# 51_V4.net
KiCad netlist of a schematic drawn in EasyEDA Pro
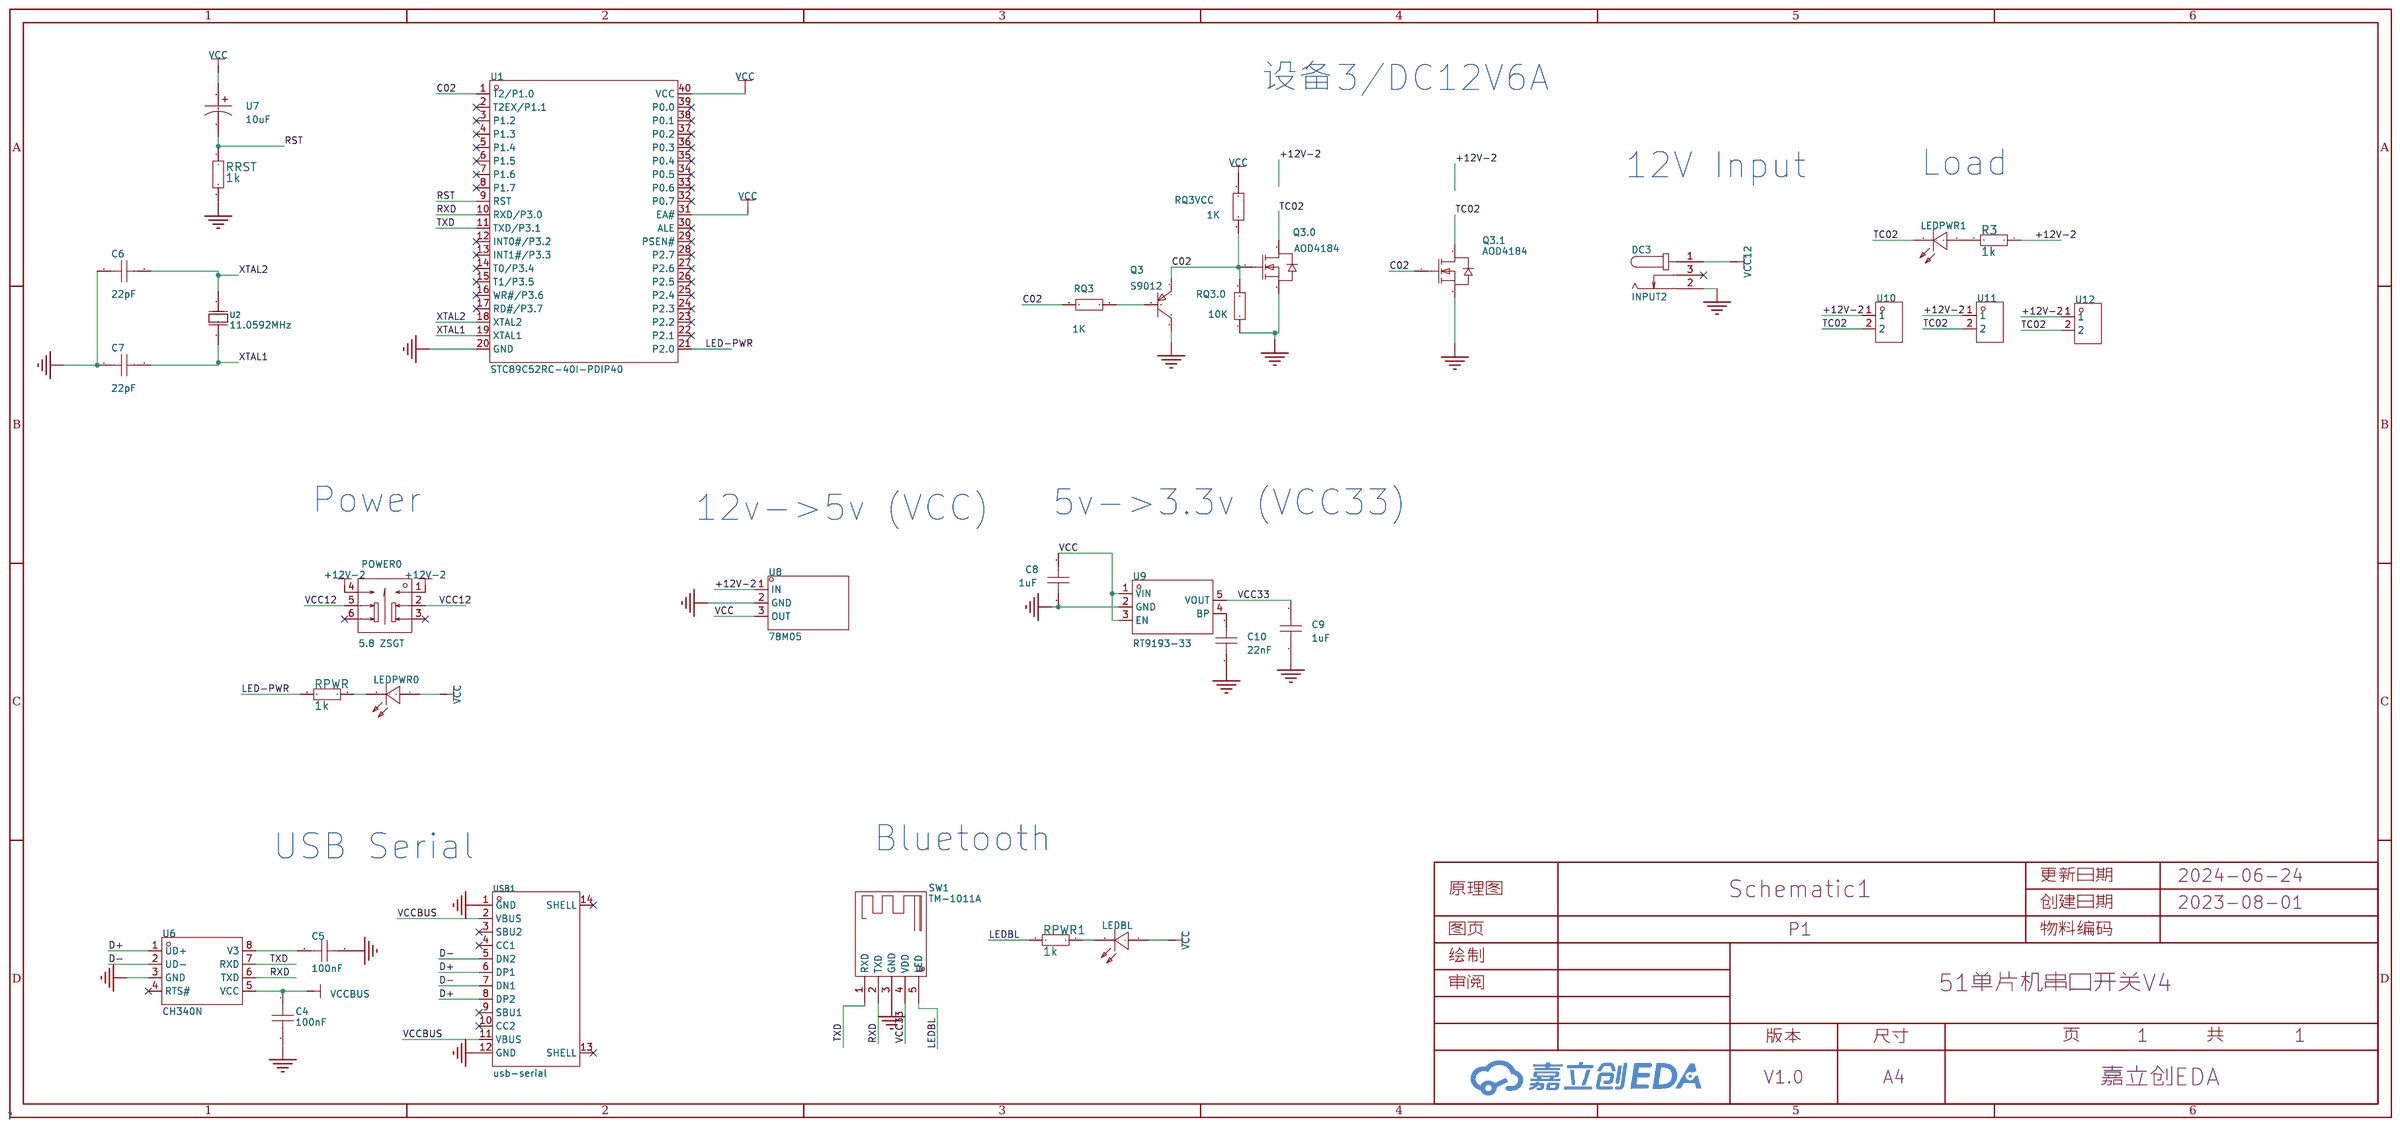
[diagram p0: schematic sheet]

(export (version "E")
  (design (tool "Eeschema 10.0.6"))
  (components
    (comp (ref "C4")
      (value "100nF")
      (footprint "easyedapro:C0603")
      (libsource (lib "easyedapro") (part "CapAcitance"))
    )
    (comp (ref "C5")
      (value "100nF")
      (footprint "easyedapro:C0603")
      (libsource (lib "easyedapro") (part "CapAcitance"))
    )
    (comp (ref "C6")
      (value "22pF")
      (footprint "easyedapro:CAP-TH_L5.8-W2.4-P2.54-D0.6")
      (description "容值:22pF;精度:±10%;额定电压:50V;温度系数:NP0;")
      (fields
        (field (name "Manufacturer Part") "CC1H220KA1EDCH4B1100")
        (field (name "Manufacturer") "Dersonic(德尔创)")
      )
      (libsource (lib "easyedapro") (part "CC1H220KA1EDCH4B1100"))
    )
    (comp (ref "C7")
      (value "22pF")
      (footprint "easyedapro:CAP-TH_L5.8-W2.4-P2.54-D0.6")
      (description "容值:22pF;精度:±10%;额定电压:50V;温度系数:NP0;")
      (fields
        (field (name "Manufacturer Part") "CC1H220KA1EDCH4B1100")
        (field (name "Manufacturer") "Dersonic(德尔创)")
      )
      (libsource (lib "easyedapro") (part "CC1H220KA1EDCH4B1100"))
    )
    (comp (ref "C8")
      (value "1uF")
      (footprint "easyedapro:C0603")
      (libsource (lib "easyedapro") (part "CapAcitance"))
    )
    (comp (ref "C9")
      (value "1uF")
      (footprint "easyedapro:C0603")
      (libsource (lib "easyedapro") (part "CapAcitance"))
    )
    (comp (ref "C10")
      (value "22nF")
      (footprint "easyedapro:C0603")
      (libsource (lib "easyedapro") (part "CapAcitance"))
    )
    (comp (ref "DC3")
      (value "INPUT2")
      (footprint "easyedapro:DC-IN-TH_DC-005-20A")
      (description "触点内径:2mm;触点外径:6.4mm;额定电流:500mA;额定电压:30V;")
      (fields (field (name "Manufacturer Part") "DC-005-20A") (field (name "Manufacturer") "韩国韩荣"))
      (libsource (lib "easyedapro") (part "DC-005-20A_C136744"))
    )
    (comp (ref "LEDBL")
      (value "Φ3mm直插蓝色发光二极管")
      (footprint "easyedapro:LED-TH_BD4.1-P2.50-D0.5-FD_BULE")
      (libsource (lib "easyedapro") (part "Φ3MM直插蓝色发光二极管"))
    )
    (comp (ref "LEDPWR0")
      (value "Φ3mm直插蓝色发光二极管")
      (footprint "easyedapro:LED-TH_BD4.1-P2.50-D0.5-FD_BULE")
      (libsource (lib "easyedapro") (part "Φ3MM直插蓝色发光二极管"))
    )
    (comp (ref "LEDPWR1")
      (value "Φ3mm直插蓝色发光二极管")
      (footprint "easyedapro:LED-TH_BD4.1-P2.50-D0.5-FD_BULE")
      (libsource (lib "easyedapro") (part "Φ3MM直插蓝色发光二极管"))
    )
    (comp (ref "POWER0")
      (value "5.8 ZSGT")
      (footprint "easyedapro:SW-TH_5.8ZSGT")
      (fields (field (name "Manufacturer") "SHOU HAN(首韩)"))
      (libsource (lib "easyedapro") (part "5.8 ZSGT"))
    )
    (comp (ref "Q3")
      (value "S9012")
      (footprint "easyedapro:TO-92-3_L4.6-W3.6-P1.27-L-1")
      (fields (field (name "Manufacturer") "JSMSEMI(杰盛微)"))
      (libsource (lib "easyedapro") (part "S9012_C2931496"))
    )
    (comp (ref "Q3.0")
      (value "AOD4184")
      (footprint "easyedapro:TO-252-2_L6.6-W6.1-P4.58-LS9.9-BR")
      (fields (field (name "Manufacturer") "VBsemi(微碧)"))
      (libsource (lib "easyedapro") (part "AOD4184"))
    )
    (comp (ref "Q3.1")
      (value "AOD4184")
      (footprint "easyedapro:TO-252-2_L6.6-W6.1-P4.58-LS9.9-BR")
      (fields (field (name "Manufacturer") "VBsemi(微碧)"))
      (libsource (lib "easyedapro") (part "AOD4184"))
    )
    (comp (ref "R3")
      (value "1k")
      (footprint "easyedapro:0603")
      (description "Resistor")
      (libsource (lib "easyedapro") (part "RES"))
    )
    (comp (ref "RPWR")
      (value "1k")
      (footprint "easyedapro:0603")
      (description "Resistor")
      (libsource (lib "easyedapro") (part "RES"))
    )
    (comp (ref "RPWR1")
      (value "1k")
      (footprint "easyedapro:0603")
      (description "Resistor")
      (libsource (lib "easyedapro") (part "RES"))
    )
    (comp (ref "RQ3") (value "1K") (footprint "easyedapro:R0603") (libsource (lib "easyedapro") (part "电阻")))
    (comp (ref "RQ3.0")
      (value "10K")
      (footprint "easyedapro:R0603")
      (libsource (lib "easyedapro") (part "电阻"))
    )
    (comp (ref "RQ3VCC")
      (value "1K")
      (footprint "easyedapro:R0603")
      (libsource (lib "easyedapro") (part "电阻"))
    )
    (comp (ref "RRST")
      (value "1k")
      (footprint "easyedapro:0603")
      (description "Resistor")
      (libsource (lib "easyedapro") (part "RES"))
    )
    (comp (ref "SW1")
      (value "TM-1011A")
      (footprint "easyedapro:SW-SMD_TM-1011A")
      (description "6328A低成本蓝牙模块")
      (fields (field (name "Manufacturer") "XKB Connectivity(中国星坤)") (field (name "NAME") "LED"))
      (libsource (lib "easyedapro") (part "邮票5孔蓝牙模块"))
    )
    (comp (ref "U1")
      (value "STC89C52RC-40I-PDIP40")
      (footprint "easyedapro:DIP-40_L52.0-W13.7-P2.54-LS15.2-BL")
      (fields (field (name "Manufacturer") "STC(宏晶)"))
      (libsource (lib "easyedapro") (part "STC89C52RC-40I"))
    )
    (comp (ref "U2")
      (value "11.0592MHz")
      (footprint "easyedapro:CRYSTAL-TH_L10.8-W4.5-P4.88")
      (description "频率:10MHz;频率公差:±30ppm;负载电容:18pF;")
      (fields (field (name "Manufacturer Part") "ATS100B-E") (field (name "Manufacturer") "CTS(西迪斯)"))
      (libsource (lib "easyedapro") (part "ATS100B-E"))
    )
    (comp (ref "U6")
      (value "CH340N")
      (footprint "easyedapro:SOP-8_L4.9-W3.9-P1.27-LS6.0-BL")
      (fields (field (name "Manufacturer") "WCH(南京沁恒)"))
      (libsource (lib "easyedapro") (part "CH340N_C2977777"))
    )
    (comp (ref "U7")
      (value "10uF")
      (footprint "easyedapro:CAP-TH_BD6.3-P2.50-D0.5-FD")
      (description "容值:10uF;精度:±20%;额定电压:50V;纹波电流:-;等效串联电阻:-;")
      (fields
        (field (name "Manufacturer Part") "ESK106M1HD11RRSNP-R")
        (field (name "Manufacturer") "MAN YUE(万裕科技)")
      )
      (libsource (lib "easyedapro") (part "ESK106M1HD11RRSNP-R"))
    )
    (comp (ref "U8")
      (value "78M05")
      (footprint "easyedapro:TO-252-2_L6.6-W6.1-P4.57-LS9.9-BR-CW")
      (description "输出类型:固定;最大输入电压:35V;输出电压:5V;最大输出电流:1A;电源纹波抑制比(PSRR):80dB@(120Hz);输出极性:正极;")
      (fields (field (name "Manufacturer") "UMW(友台半导体)"))
      (libsource (lib "easyedapro") (part "UMW78M05"))
    )
    (comp (ref "U9")
      (value "RT9193-33")
      (footprint "easyedapro:SOT-23-5_L2.9-W1.6-P0.95-LS2.8-BL")
      (libsource (lib "easyedapro") (part "RT9193-33"))
    )
    (comp (ref "U10")
      (value "HX 2.54mm-2P ZZ-MS")
      (footprint "easyedapro:CONN-TH_2P-P2.50_HX-2.54MM-2P-ZZ-MS")
      (description "插针结构:1x2P;间距:2.5mm;安装方式:直插;参考系列:XH;总PIN数:2P;排数:1;每排PIN数:2;额定电流:3A;工作温度范围:-25°C~+85°C;")
      (fields (field (name "Manufacturer") "hanxia(韩下)"))
      (libsource (lib "easyedapro") (part "HX 2.54MM-2P ZZ-MS"))
    )
    (comp (ref "U11")
      (value "HX 2.54mm-2P ZZ-MS")
      (footprint "easyedapro:CONN-TH_2P-P2.50_HX-2.54MM-2P-ZZ-MS")
      (description "插针结构:1x2P;间距:2.5mm;安装方式:直插;参考系列:XH;总PIN数:2P;排数:1;每排PIN数:2;额定电流:3A;工作温度范围:-25°C~+85°C;")
      (fields (field (name "Manufacturer") "hanxia(韩下)"))
      (libsource (lib "easyedapro") (part "HX 2.54MM-2P ZZ-MS"))
    )
    (comp (ref "U12")
      (value "HX 2.54mm-2P ZZ-MS")
      (footprint "easyedapro:CONN-TH_2P-P2.50_HX-2.54MM-2P-ZZ-MS")
      (description "插针结构:1x2P;间距:2.5mm;安装方式:直插;参考系列:XH;总PIN数:2P;排数:1;每排PIN数:2;额定电流:3A;工作温度范围:-25°C~+85°C;")
      (fields (field (name "Manufacturer") "hanxia(韩下)"))
      (libsource (lib "easyedapro") (part "HX 2.54MM-2P ZZ-MS"))
    )
    (comp (ref "USB1")
      (value "usb-serial")
      (footprint "easyedapro:USB-C-SMD_TYPE-C-6PIN-2MD-073")
      (description "连接器类型:Type-C;标准:-;公母:母座;触点数量:16;端口数量:1;安装方式:卧贴;额定电流 - 电源:5A;工作温度范围:-25°C~+85°C;")
      (fields
        (field (name "Manufacturer Part") "TYPE-C 16PIN 2MD(073)")
        (field (name "Manufacturer") "SHOU HAN(首韩)")
      )
      (libsource (lib "easyedapro") (part "TYPE-C 16PIN 2MD(073)"))
    )
  )
  (nets
    (net (code "1") (name "+12V-2") (class "Default")
      (node (ref "POWER0") (pin "1") (pinfunction "1_1") (pintype "input"))
      (node (ref "POWER0") (pin "4") (pinfunction "4_4") (pintype "input"))
      (node (ref "R3") (pin "1") (pinfunction "1_1") (pintype "input"))
      (node (ref "U10") (pin "1") (pinfunction "1_1") (pintype "unspecified"))
      (node (ref "U11") (pin "1") (pinfunction "1_1") (pintype "unspecified"))
      (node (ref "U12") (pin "1") (pinfunction "1_1") (pintype "unspecified"))
      (node (ref "U8") (pin "1") (pinfunction "IN_1") (pintype "unspecified"))
    )
    (net (code "2") (name "/C02") (class "Default")
      (node (ref "Q3") (pin "1") (pinfunction "E_1") (pintype "input"))
      (node (ref "Q3.0") (pin "1") (pinfunction "G_1") (pintype "input"))
      (node (ref "Q3.1") (pin "1") (pinfunction "G_1") (pintype "input"))
      (node (ref "RQ3") (pin "2") (pinfunction "2_2") (pintype "input"))
      (node (ref "RQ3.0") (pin "2") (pinfunction "2_2") (pintype "input"))
      (node (ref "RQ3VCC") (pin "1") (pinfunction "1_1") (pintype "input"))
      (node (ref "U1") (pin "1") (pinfunction "T2/P1.0_1") (pintype "input"))
    )
    (net (code "3") (name "/D+") (class "Default")
      (node (ref "U6") (pin "1") (pinfunction "UD+_1") (pintype "input"))
      (node (ref "USB1") (pin "6") (pinfunction "DP1_6") (pintype "input"))
      (node (ref "USB1") (pin "8") (pinfunction "DP2_8") (pintype "input"))
    )
    (net (code "4") (name "/D-") (class "Default")
      (node (ref "U6") (pin "2") (pinfunction "UD-_2") (pintype "input"))
      (node (ref "USB1") (pin "5") (pinfunction "DN2_5") (pintype "input"))
      (node (ref "USB1") (pin "7") (pinfunction "DN1_7") (pintype "input"))
    )
    (net (code "5") (name "/LED-PWR") (class "Default")
      (node (ref "RPWR") (pin "2") (pinfunction "2_2") (pintype "input"))
      (node (ref "U1") (pin "21") (pinfunction "P2.0_21") (pintype "input"))
    )
    (net (code "6") (name "/LEDBL") (class "Default")
      (node (ref "RPWR1") (pin "2") (pinfunction "2_2") (pintype "input"))
      (node (ref "SW1") (pin "5") (pinfunction "LED_5") (pintype "input"))
    )
    (net (code "7") (name "/RST") (class "Default")
      (node (ref "RRST") (pin "1") (pinfunction "1_1") (pintype "input"))
      (node (ref "U1") (pin "9") (pinfunction "RST_9") (pintype "input"))
      (node (ref "U7") (pin "2") (pinfunction "2_2") (pintype "input"))
    )
    (net (code "8") (name "/RXD") (class "Default")
      (node (ref "SW1") (pin "2") (pinfunction "TXD_2") (pintype "input"))
      (node (ref "U1") (pin "10") (pinfunction "RXD/P3.0_10") (pintype "input"))
      (node (ref "U6") (pin "6") (pinfunction "TXD_6") (pintype "input"))
    )
    (net (code "9") (name "/TC02") (class "Default")
      (node (ref "LEDPWR1") (pin "2") (pinfunction "-_2") (pintype "input"))
      (node (ref "Q3.0") (pin "2") (pinfunction "D_2") (pintype "input"))
      (node (ref "Q3.1") (pin "2") (pinfunction "D_2") (pintype "input"))
      (node (ref "U10") (pin "2") (pinfunction "2_2") (pintype "unspecified"))
      (node (ref "U11") (pin "2") (pinfunction "2_2") (pintype "unspecified"))
      (node (ref "U12") (pin "2") (pinfunction "2_2") (pintype "unspecified"))
    )
    (net (code "10") (name "/TXD") (class "Default")
      (node (ref "SW1") (pin "1") (pinfunction "RXD_1") (pintype "input"))
      (node (ref "U1") (pin "11") (pinfunction "TXD/P3.1_11") (pintype "input"))
      (node (ref "U6") (pin "7") (pinfunction "RXD_7") (pintype "input"))
    )
    (net (code "11") (name "/VCC33") (class "Default")
      (node (ref "C9") (pin "2") (pinfunction "2_2") (pintype "input"))
      (node (ref "SW1") (pin "4") (pinfunction "VDD_4") (pintype "input"))
      (node (ref "U9") (pin "5") (pinfunction "VOUT_5") (pintype "unspecified"))
    )
    (net (code "12") (name "/XTAL1") (class "Default")
      (node (ref "C7") (pin "2") (pinfunction "2_2") (pintype "input"))
      (node (ref "U1") (pin "19") (pinfunction "XTAL1_19") (pintype "input"))
      (node (ref "U2") (pin "2") (pinfunction "2_2") (pintype "input"))
    )
    (net (code "13") (name "/XTAL2") (class "Default")
      (node (ref "C6") (pin "2") (pinfunction "2_2") (pintype "input"))
      (node (ref "U1") (pin "18") (pinfunction "XTAL2_18") (pintype "input"))
      (node (ref "U2") (pin "1") (pinfunction "1_1") (pintype "input"))
    )
    (net (code "14") (name "GND") (class "Default")
      (node (ref "C10") (pin "1") (pinfunction "1_1") (pintype "input"))
      (node (ref "C4") (pin "2") (pinfunction "2_2") (pintype "input"))
      (node (ref "C5") (pin "2") (pinfunction "2_2") (pintype "input"))
      (node (ref "C6") (pin "1") (pinfunction "1_1") (pintype "input"))
      (node (ref "C7") (pin "1") (pinfunction "1_1") (pintype "input"))
      (node (ref "C8") (pin "2") (pinfunction "2_2") (pintype "input"))
      (node (ref "C9") (pin "1") (pinfunction "1_1") (pintype "input"))
      (node (ref "DC3") (pin "2") (pinfunction "2_2") (pintype "input"))
      (node (ref "Q3") (pin "3") (pinfunction "C_3") (pintype "input"))
      (node (ref "Q3.0") (pin "3") (pinfunction "S_3") (pintype "input"))
      (node (ref "Q3.1") (pin "3") (pinfunction "S_3") (pintype "input"))
      (node (ref "RQ3.0") (pin "1") (pinfunction "1_1") (pintype "input"))
      (node (ref "RRST") (pin "2") (pinfunction "2_2") (pintype "input"))
      (node (ref "SW1") (pin "3") (pinfunction "GND_3") (pintype "input"))
      (node (ref "U1") (pin "20") (pinfunction "GND_20") (pintype "input"))
      (node (ref "U6") (pin "3") (pinfunction "GND_3") (pintype "input"))
      (node (ref "U8") (pin "2") (pinfunction "GND_2") (pintype "unspecified"))
      (node (ref "U9") (pin "2") (pinfunction "GND_2") (pintype "unspecified"))
      (node (ref "USB1") (pin "1") (pinfunction "GND_1") (pintype "input"))
      (node (ref "USB1") (pin "12") (pinfunction "GND_12") (pintype "input"))
    )
    (net (code "15") (name "Net-(LEDBL--)") (class "Default")
      (node (ref "LEDBL") (pin "2") (pinfunction "-_2") (pintype "input"))
      (node (ref "RPWR1") (pin "1") (pinfunction "1_1") (pintype "input"))
    )
    (net (code "16") (name "Net-(LEDPWR0--)") (class "Default")
      (node (ref "LEDPWR0") (pin "2") (pinfunction "-_2") (pintype "input"))
      (node (ref "RPWR") (pin "1") (pinfunction "1_1") (pintype "input"))
    )
    (net (code "17") (name "Net-(LEDPWR1-+)") (class "Default")
      (node (ref "LEDPWR1") (pin "1") (pinfunction "+_1") (pintype "input"))
      (node (ref "R3") (pin "2") (pinfunction "2_2") (pintype "input"))
    )
    (net (code "18") (name "Net-(Q3-B)") (class "Default")
      (node (ref "Q3") (pin "2") (pinfunction "B_2") (pintype "input"))
      (node (ref "RQ3") (pin "1") (pinfunction "1_1") (pintype "input"))
    )
    (net (code "19") (name "Net-(U6-V3)") (class "Default")
      (node (ref "C5") (pin "1") (pinfunction "1_1") (pintype "input"))
      (node (ref "U6") (pin "8") (pinfunction "V3_8") (pintype "input"))
    )
    (net (code "20") (name "Net-(U9-BP)") (class "Default")
      (node (ref "C10") (pin "2") (pinfunction "2_2") (pintype "input"))
      (node (ref "U9") (pin "4") (pinfunction "BP_4") (pintype "unspecified"))
    )
    (net (code "21") (name "VCC") (class "Default")
      (node (ref "C8") (pin "1") (pinfunction "1_1") (pintype "input"))
      (node (ref "LEDBL") (pin "1") (pinfunction "+_1") (pintype "input"))
      (node (ref "LEDPWR0") (pin "1") (pinfunction "+_1") (pintype "input"))
      (node (ref "RQ3VCC") (pin "2") (pinfunction "2_2") (pintype "input"))
      (node (ref "U1") (pin "31") (pinfunction "EA#_31") (pintype "input"))
      (node (ref "U1") (pin "40") (pinfunction "VCC_40") (pintype "input"))
      (node (ref "U7") (pin "1") (pinfunction "1_1") (pintype "input"))
      (node (ref "U8") (pin "3") (pinfunction "OUT_3") (pintype "unspecified"))
      (node (ref "U9") (pin "1") (pinfunction "VIN_1") (pintype "unspecified"))
      (node (ref "U9") (pin "3") (pinfunction "EN_3") (pintype "unspecified"))
    )
    (net (code "22") (name "VCC12") (class "Default")
      (node (ref "DC3") (pin "1") (pinfunction "1_1") (pintype "input"))
      (node (ref "POWER0") (pin "2") (pinfunction "2_2") (pintype "input"))
      (node (ref "POWER0") (pin "5") (pinfunction "5_5") (pintype "input"))
    )
    (net (code "23") (name "VCCBUS") (class "Default")
      (node (ref "C4") (pin "1") (pinfunction "1_1") (pintype "input"))
      (node (ref "U6") (pin "5") (pinfunction "VCC_5") (pintype "input"))
      (node (ref "USB1") (pin "11") (pinfunction "VBUS_11") (pintype "input"))
      (node (ref "USB1") (pin "2") (pinfunction "VBUS_2") (pintype "input"))
    )
    (net (code "24") (name "unconnected-(DC3-Pad3)") (class "Default")
      (node (ref "DC3") (pin "3") (pinfunction "3_3") (pintype "input+no_connect"))
    )
    (net (code "25") (name "unconnected-(POWER0-Pad3)") (class "Default")
      (node (ref "POWER0") (pin "3") (pinfunction "3_3") (pintype "input+no_connect"))
    )
    (net (code "26") (name "unconnected-(POWER0-Pad6)") (class "Default")
      (node (ref "POWER0") (pin "6") (pinfunction "6_6") (pintype "input+no_connect"))
    )
    (net (code "27") (name "unconnected-(U1-ALE-Pad30)") (class "Default")
      (node (ref "U1") (pin "30") (pinfunction "ALE_30") (pintype "input+no_connect"))
    )
    (net (code "28") (name "unconnected-(U1-INT0#{slash}P3.2-Pad12)") (class "Default")
      (node (ref "U1") (pin "12") (pinfunction "INT0#/P3.2_12") (pintype "input+no_connect"))
    )
    (net (code "29") (name "unconnected-(U1-INT1#{slash}P3.3-Pad13)") (class "Default")
      (node (ref "U1") (pin "13") (pinfunction "INT1#/P3.3_13") (pintype "input+no_connect"))
    )
    (net (code "30") (name "unconnected-(U1-P0.0-Pad39)") (class "Default")
      (node (ref "U1") (pin "39") (pinfunction "P0.0_39") (pintype "input+no_connect"))
    )
    (net (code "31") (name "unconnected-(U1-P0.1-Pad38)") (class "Default")
      (node (ref "U1") (pin "38") (pinfunction "P0.1_38") (pintype "input+no_connect"))
    )
    (net (code "32") (name "unconnected-(U1-P0.2-Pad37)") (class "Default")
      (node (ref "U1") (pin "37") (pinfunction "P0.2_37") (pintype "input+no_connect"))
    )
    (net (code "33") (name "unconnected-(U1-P0.3-Pad36)") (class "Default")
      (node (ref "U1") (pin "36") (pinfunction "P0.3_36") (pintype "input+no_connect"))
    )
    (net (code "34") (name "unconnected-(U1-P0.4-Pad35)") (class "Default")
      (node (ref "U1") (pin "35") (pinfunction "P0.4_35") (pintype "input+no_connect"))
    )
    (net (code "35") (name "unconnected-(U1-P0.5-Pad34)") (class "Default")
      (node (ref "U1") (pin "34") (pinfunction "P0.5_34") (pintype "input+no_connect"))
    )
    (net (code "36") (name "unconnected-(U1-P0.6-Pad33)") (class "Default")
      (node (ref "U1") (pin "33") (pinfunction "P0.6_33") (pintype "input+no_connect"))
    )
    (net (code "37") (name "unconnected-(U1-P0.7-Pad32)") (class "Default")
      (node (ref "U1") (pin "32") (pinfunction "P0.7_32") (pintype "input+no_connect"))
    )
    (net (code "38") (name "unconnected-(U1-P1.2-Pad3)") (class "Default")
      (node (ref "U1") (pin "3") (pinfunction "P1.2_3") (pintype "input+no_connect"))
    )
    (net (code "39") (name "unconnected-(U1-P1.3-Pad4)") (class "Default")
      (node (ref "U1") (pin "4") (pinfunction "P1.3_4") (pintype "input+no_connect"))
    )
    (net (code "40") (name "unconnected-(U1-P1.4-Pad5)") (class "Default")
      (node (ref "U1") (pin "5") (pinfunction "P1.4_5") (pintype "input+no_connect"))
    )
    (net (code "41") (name "unconnected-(U1-P1.5-Pad6)") (class "Default")
      (node (ref "U1") (pin "6") (pinfunction "P1.5_6") (pintype "input+no_connect"))
    )
    (net (code "42") (name "unconnected-(U1-P1.6-Pad7)") (class "Default")
      (node (ref "U1") (pin "7") (pinfunction "P1.6_7") (pintype "input+no_connect"))
    )
    (net (code "43") (name "unconnected-(U1-P1.7-Pad8)") (class "Default")
      (node (ref "U1") (pin "8") (pinfunction "P1.7_8") (pintype "input+no_connect"))
    )
    (net (code "44") (name "unconnected-(U1-P2.1-Pad22)") (class "Default")
      (node (ref "U1") (pin "22") (pinfunction "P2.1_22") (pintype "input+no_connect"))
    )
    (net (code "45") (name "unconnected-(U1-P2.2-Pad23)") (class "Default")
      (node (ref "U1") (pin "23") (pinfunction "P2.2_23") (pintype "input+no_connect"))
    )
    (net (code "46") (name "unconnected-(U1-P2.3-Pad24)") (class "Default")
      (node (ref "U1") (pin "24") (pinfunction "P2.3_24") (pintype "input+no_connect"))
    )
    (net (code "47") (name "unconnected-(U1-P2.4-Pad25)") (class "Default")
      (node (ref "U1") (pin "25") (pinfunction "P2.4_25") (pintype "input+no_connect"))
    )
    (net (code "48") (name "unconnected-(U1-P2.5-Pad26)") (class "Default")
      (node (ref "U1") (pin "26") (pinfunction "P2.5_26") (pintype "input+no_connect"))
    )
    (net (code "49") (name "unconnected-(U1-P2.6-Pad27)") (class "Default")
      (node (ref "U1") (pin "27") (pinfunction "P2.6_27") (pintype "input+no_connect"))
    )
    (net (code "50") (name "unconnected-(U1-P2.7-Pad28)") (class "Default")
      (node (ref "U1") (pin "28") (pinfunction "P2.7_28") (pintype "input+no_connect"))
    )
    (net (code "51") (name "unconnected-(U1-PSEN#-Pad29)") (class "Default")
      (node (ref "U1") (pin "29") (pinfunction "PSEN#_29") (pintype "input+no_connect"))
    )
    (net (code "52") (name "unconnected-(U1-RD#{slash}P3.7-Pad17)") (class "Default")
      (node (ref "U1") (pin "17") (pinfunction "RD#/P3.7_17") (pintype "input+no_connect"))
    )
    (net (code "53") (name "unconnected-(U1-T0{slash}P3.4-Pad14)") (class "Default")
      (node (ref "U1") (pin "14") (pinfunction "T0/P3.4_14") (pintype "input+no_connect"))
    )
    (net (code "54") (name "unconnected-(U1-T1{slash}P3.5-Pad15)") (class "Default")
      (node (ref "U1") (pin "15") (pinfunction "T1/P3.5_15") (pintype "input+no_connect"))
    )
    (net (code "55") (name "unconnected-(U1-T2EX{slash}P1.1-Pad2)") (class "Default")
      (node (ref "U1") (pin "2") (pinfunction "T2EX/P1.1_2") (pintype "input+no_connect"))
    )
    (net (code "56") (name "unconnected-(U1-WR#{slash}P3.6-Pad16)") (class "Default")
      (node (ref "U1") (pin "16") (pinfunction "WR#/P3.6_16") (pintype "input+no_connect"))
    )
    (net (code "57") (name "unconnected-(U6-RTS#-Pad4)") (class "Default")
      (node (ref "U6") (pin "4") (pinfunction "RTS#_4") (pintype "input+no_connect"))
    )
    (net (code "58") (name "unconnected-(USB1-CC1-Pad4)") (class "Default")
      (node (ref "USB1") (pin "4") (pinfunction "CC1_4") (pintype "input+no_connect"))
    )
    (net (code "59") (name "unconnected-(USB1-CC2-Pad10)") (class "Default")
      (node (ref "USB1") (pin "10") (pinfunction "CC2_10") (pintype "input+no_connect"))
    )
    (net (code "60") (name "unconnected-(USB1-SBU1-Pad9)") (class "Default")
      (node (ref "USB1") (pin "9") (pinfunction "SBU1_9") (pintype "input+no_connect"))
    )
    (net (code "61") (name "unconnected-(USB1-SBU2-Pad3)") (class "Default")
      (node (ref "USB1") (pin "3") (pinfunction "SBU2_3") (pintype "input+no_connect"))
    )
    (net (code "62") (name "unconnected-(USB1-SHELL-Pad13)") (class "Default")
      (node (ref "USB1") (pin "13") (pinfunction "SHELL_13") (pintype "input+no_connect"))
    )
    (net (code "63") (name "unconnected-(USB1-SHELL-Pad14)") (class "Default")
      (node (ref "USB1") (pin "14") (pinfunction "SHELL_14") (pintype "input+no_connect"))
    )
  )
)
